# guangmin.net
KiCad netlist of a schematic drawn in Altium Designer
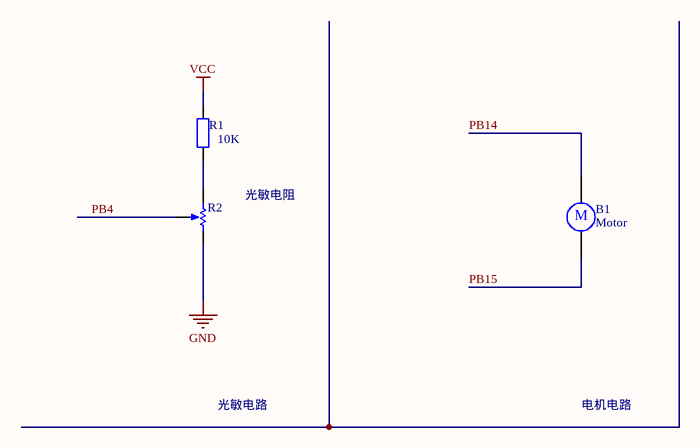
[diagram p0: guangmin.SchDoc]

(export (version "E")
  (design (tool "Eeschema 10.0.6"))
  (components
    (comp (ref "B1")
      (value "Motor")
      (footprint "RB5-10.5")
      (description "Motor, General Kind")
      (fields (field (name "PUBLISHER") "Altium Limited"))
      (libsource (lib "Miscellaneous Devices") (part "Motor"))
    )
    (comp (ref "R1")
      (value "10K")
      (footprint "AXIAL-0.4")
      (description "Resistor")
      (fields (field (name "Comment") "Res2") (field (name "PUBLISHER") "Altium Limited"))
      (libsource (lib "Miscellaneous Devices") (part "Res2"))
    )
    (comp (ref "R2")
      (value "RPot")
      (footprint "VR5")
      (description "Potentiometer")
      (fields (field (name "PUBLISHER") "Altium Limited"))
      (libsource (lib "Miscellaneous Devices") (part "RPot"))
    )
  )
  (nets
    (net (code "1") (name "/PB4") (class "Default")
      (node (ref "R2") (pin "3") (pinfunction "TAP_3") (pintype "passive"))
    )
    (net (code "2") (name "/PB14") (class "Default")
      (node (ref "B1") (pin "1") (pinfunction "1_1") (pintype "passive"))
    )
    (net (code "3") (name "/PB15") (class "Default")
      (node (ref "B1") (pin "2") (pinfunction "2_2") (pintype "passive"))
    )
    (net (code "4") (name "GND") (class "Default")
      (node (ref "R2") (pin "2") (pinfunction "BOT_2") (pintype "passive"))
    )
    (net (code "5") (name "Net-(R2-TOP)") (class "Default")
      (node (ref "R1") (pin "1") (pinfunction "1_1") (pintype "passive"))
      (node (ref "R2") (pin "1") (pinfunction "TOP_1") (pintype "passive"))
    )
    (net (code "6") (name "VCC") (class "Default")
      (node (ref "R1") (pin "2") (pinfunction "2_2") (pintype "passive"))
    )
  )
)
